# Schematic_proiect_v15.net
KiCad netlist of a schematic drawn in EAGLE
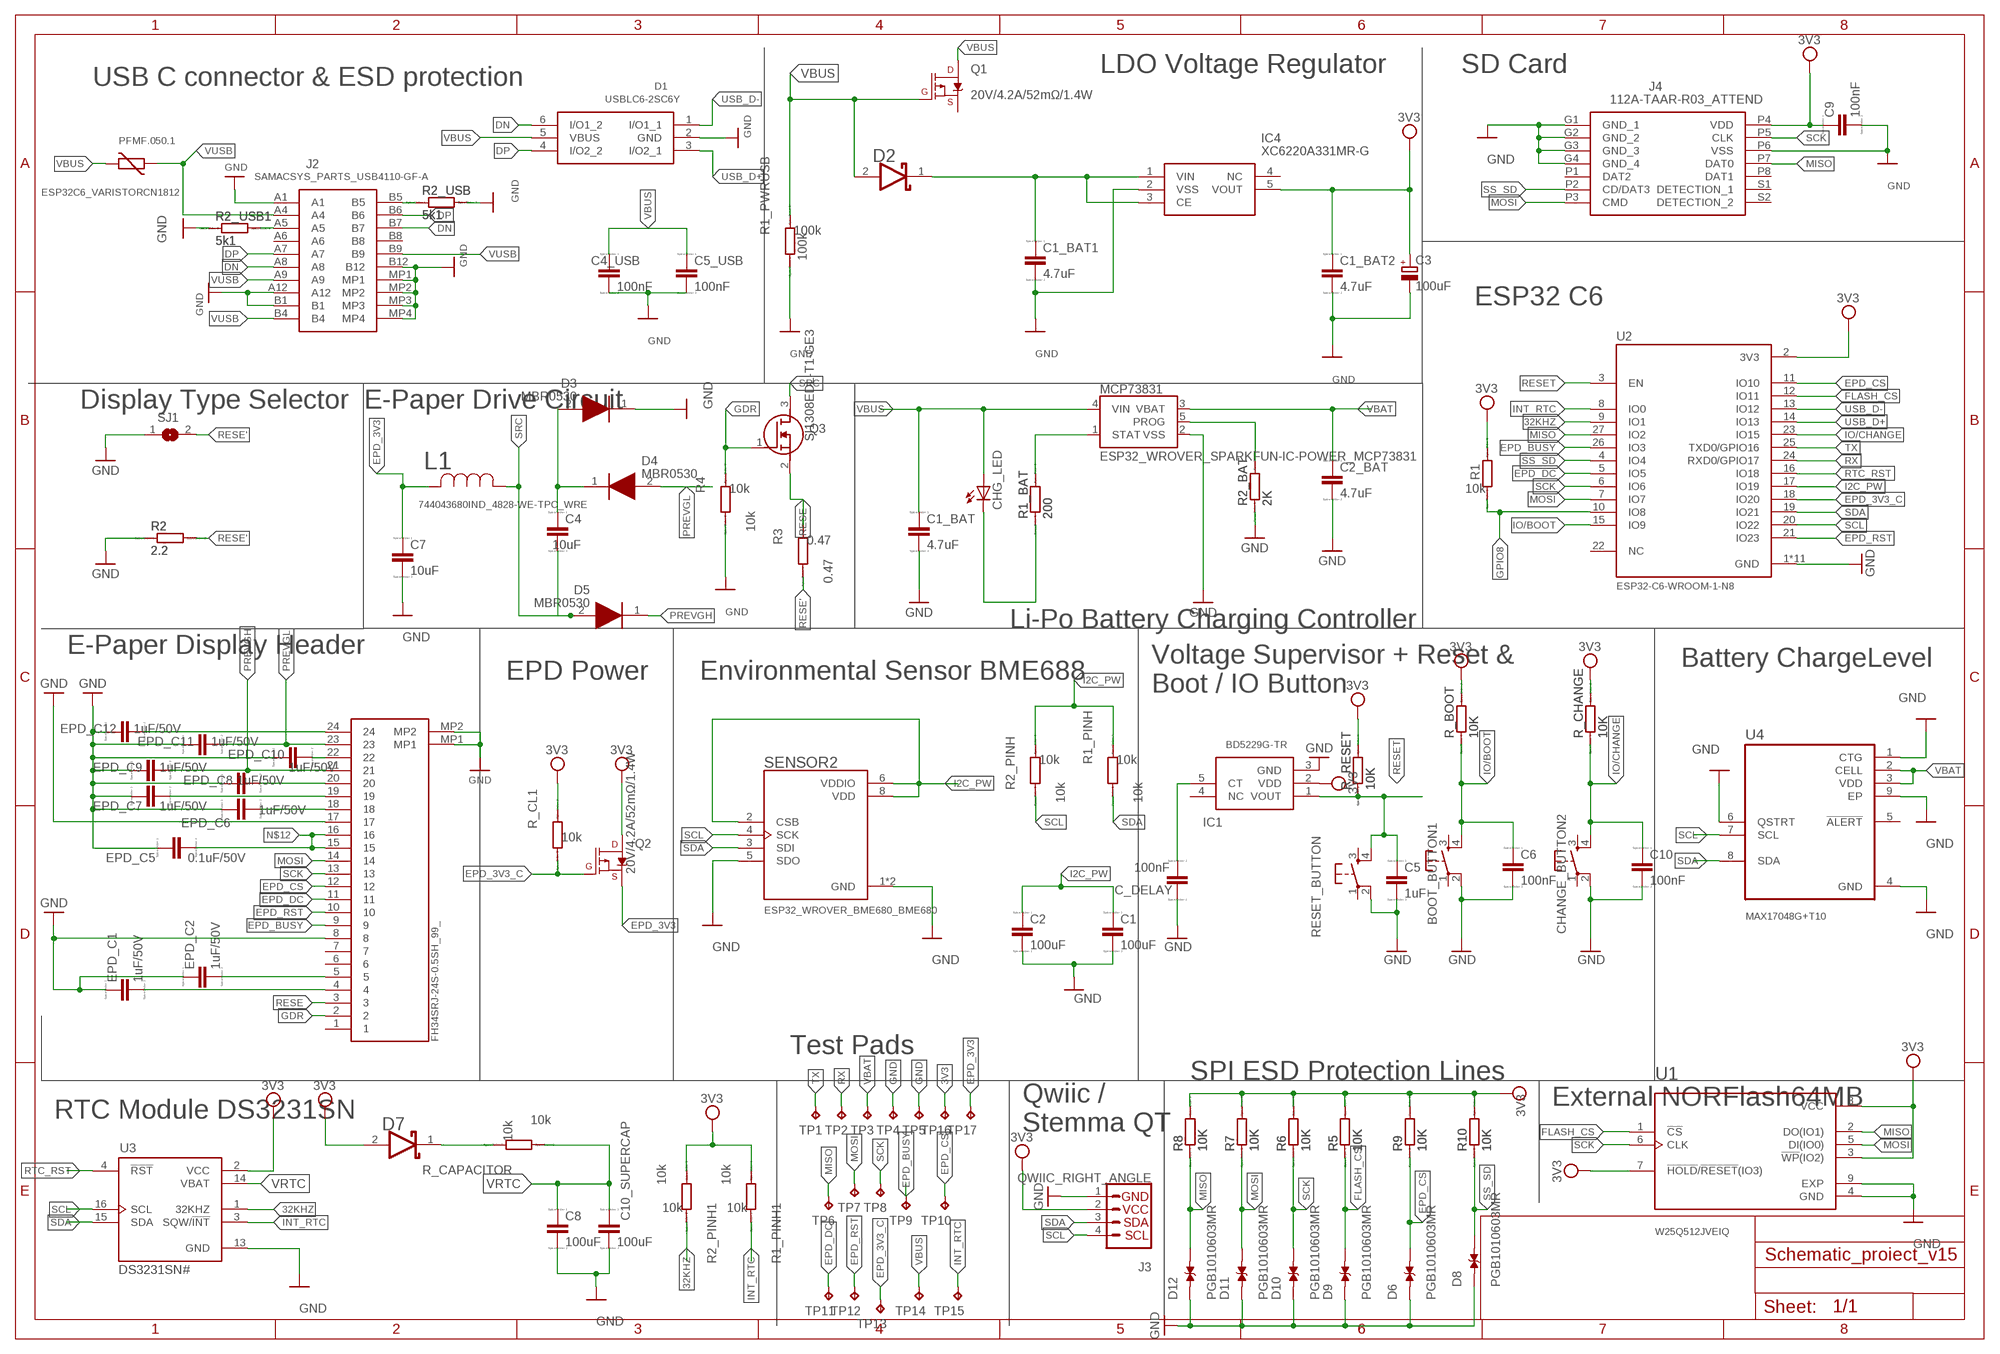
[diagram p0: schematic, sheet 1]

(export (version "E")
  (design (tool "Eeschema 10.0.6"))
  (components
    (comp (ref "BOOT_BUTTON1")
      (value "BUTTON_CUSYOMV1")
      (footprint "eagle-import:MYBUTTON")
      (libsource (lib "eagle-import") (part "BUTTON_CUSYOMV1"))
    )
    (comp (ref "C1")
      (value "100uF")
      (footprint "eagle-import:EAGLE-LTSPICE_C0402")
      (libsource (lib "eagle-import") (part "DeskAssistant v19 v1_vf.nBZE1evWTd-OCEZQXOw4Cw_EAGLE-LTSPICE_CC0402"))
    )
    (comp (ref "C1_BAT")
      (value "4.7uF")
      (footprint "eagle-import:EAGLE-LTSPICE_C0402")
      (libsource (lib "eagle-import") (part "EAGLE-LTSPICE_CC0402"))
    )
    (comp (ref "C1_BAT1")
      (value "4.7uF")
      (footprint "eagle-import:EAGLE-LTSPICE_C0402")
      (libsource (lib "eagle-import") (part "DeskAssistant v19 v1_vf.nBZE1evWTd-OCEZQXOw4Cw_EAGLE-LTSPICE_CC0402"))
    )
    (comp (ref "C1_BAT2")
      (value "4.7uF")
      (footprint "eagle-import:EAGLE-LTSPICE_C0402")
      (libsource (lib "eagle-import") (part "DeskAssistant v19 v1_vf.nBZE1evWTd-OCEZQXOw4Cw_EAGLE-LTSPICE_CC0402"))
    )
    (comp (ref "C2")
      (value "100uF")
      (footprint "eagle-import:EAGLE-LTSPICE_C0402")
      (libsource (lib "eagle-import") (part "DeskAssistant v19 v1_vf.nBZE1evWTd-OCEZQXOw4Cw_EAGLE-LTSPICE_CC0402"))
    )
    (comp (ref "C2_BAT")
      (value "4.7uF")
      (footprint "eagle-import:EAGLE-LTSPICE_C0402")
      (libsource (lib "eagle-import") (part "EAGLE-LTSPICE_CC0402"))
    )
    (comp (ref "C3")
      (value "100uF")
      (footprint "eagle-import:RCL_CT3528")
      (libsource (lib "eagle-import") (part "RCL_CPOL-EUCT3528"))
    )
    (comp (ref "C4")
      (value "10uF")
      (footprint "eagle-import:EAGLE-LTSPICE_C0402")
      (libsource (lib "eagle-import") (part "DeskAssistant v19 v1_vf.nBZE1evWTd-OCEZQXOw4Cw_EAGLE-LTSPICE_CC0402"))
    )
    (comp (ref "C4_USB")
      (value "100nF")
      (footprint "eagle-import:EAGLE-LTSPICE_C0402")
      (libsource (lib "eagle-import") (part "DeskAssistant v19 v1_vf.nBZE1evWTd-OCEZQXOw4Cw_EAGLE-LTSPICE_CC0402"))
    )
    (comp (ref "C5")
      (value "1uF")
      (footprint "eagle-import:EAGLE-LTSPICE_C0402")
      (libsource (lib "eagle-import") (part "EAGLE-LTSPICE_CC0402"))
    )
    (comp (ref "C5_USB")
      (value "100nF")
      (footprint "eagle-import:EAGLE-LTSPICE_C0402")
      (libsource (lib "eagle-import") (part "DeskAssistant v19 v1_vf.nBZE1evWTd-OCEZQXOw4Cw_EAGLE-LTSPICE_CC0402"))
    )
    (comp (ref "C6")
      (value "100nF")
      (footprint "eagle-import:EAGLE-LTSPICE_C0402")
      (libsource (lib "eagle-import") (part "EAGLE-LTSPICE_CC0402"))
    )
    (comp (ref "C7")
      (value "10uF")
      (footprint "eagle-import:EAGLE-LTSPICE_C0402")
      (libsource (lib "eagle-import") (part "DeskAssistant v19 v1_vf.nBZE1evWTd-OCEZQXOw4Cw_EAGLE-LTSPICE_CC0402"))
    )
    (comp (ref "C8")
      (value "100uF")
      (footprint "eagle-import:EAGLE-LTSPICE_C0402")
      (libsource (lib "eagle-import") (part "DeskAssistant v19 v1_vf.nBZE1evWTd-OCEZQXOw4Cw_EAGLE-LTSPICE_CC0402"))
    )
    (comp (ref "C9")
      (value "100nF")
      (footprint "eagle-import:EAGLE-LTSPICE_C0402")
      (libsource (lib "eagle-import") (part "DeskAssistant v19 v1_vf.nBZE1evWTd-OCEZQXOw4Cw_EAGLE-LTSPICE_CC0402"))
    )
    (comp (ref "C10")
      (value "100nF")
      (footprint "eagle-import:EAGLE-LTSPICE_C0402")
      (libsource (lib "eagle-import") (part "EAGLE-LTSPICE_CC0402"))
    )
    (comp (ref "C10_SUPERCAP")
      (value "100uF")
      (footprint "eagle-import:EAGLE-LTSPICE_C0402")
      (libsource (lib "eagle-import") (part "DeskAssistant v19 v1_vf.nBZE1evWTd-OCEZQXOw4Cw_EAGLE-LTSPICE_CC0402"))
    )
    (comp (ref "CHANGE_BUTTON2")
      (value "BUTTON_CUSYOMV1")
      (footprint "eagle-import:MYBUTTON")
      (libsource (lib "eagle-import") (part "BUTTON_CUSYOMV1"))
    )
    (comp (ref "CHG_LED")
      (value "ADAFRUIT_LEDCHIP-LED0603")
      (footprint "eagle-import:ADAFRUIT_CHIP-LED0603")
      (libsource (lib "eagle-import") (part "ADAFRUIT_LEDCHIP-LED0603"))
    )
    (comp (ref "C_DELAY")
      (value "100nF")
      (footprint "eagle-import:EAGLE-LTSPICE_C0402")
      (libsource (lib "eagle-import") (part "EAGLE-LTSPICE_CC0402"))
    )
    (comp (ref "D1")
      (value "USBLC6-2SC6Y")
      (footprint "eagle-import:SOT95P280X145-6N")
      (fields (field (name "MF") "STMicroelectronics"))
      (libsource (lib "eagle-import") (part "USBLC6-2SC6Y"))
    )
    (comp (ref "D2")
      (value "ESP32_WROVER_AVX---SD0805S020S1R0_AVX_SD0805S020S1R0_0_0AVX_SD0805S020S1R0_0_0")
      (footprint "eagle-import:ESP32_WROVER_AVX---SD0805S020S1R0_AVX_SD0805S020S1R0_0")
      (fields
        (field (name "DIGIKEY_PART_NUMBER") "478-7800-1-ND")
        (field (name "MF") "AVX")
        (field (name "MOUSER_PART_NUMBER") "581-SD0805S020S1R0")
      )
      (libsource (lib "eagle-import") (part "ESP32_WROVER_AVX---SD0805S020S1R0_AVX_SD0805S020S1R0_0_0AVX_SD0805S020S1R0_0_0"))
    )
    (comp (ref "D3")
      (value "MBR0530")
      (footprint "eagle-import:SOD3716X135N")
      (fields (field (name "MF") "ON Semiconductor"))
      (libsource (lib "eagle-import") (part "MBR0530"))
    )
    (comp (ref "D4")
      (value "MBR0530")
      (footprint "eagle-import:SOD3716X135N")
      (fields (field (name "MF") "ON Semiconductor"))
      (libsource (lib "eagle-import") (part "MBR0530"))
    )
    (comp (ref "D5")
      (value "MBR0530")
      (footprint "eagle-import:SOD3716X135N")
      (fields (field (name "MF") "ON Semiconductor"))
      (libsource (lib "eagle-import") (part "MBR0530"))
    )
    (comp (ref "D6")
      (value "PGB1010603MR")
      (footprint "eagle-import:DIOC1608X36N")
      (fields (field (name "MF") "Littelfuse Inc."))
      (libsource (lib "eagle-import") (part "PGB1010603MR"))
    )
    (comp (ref "D7")
      (value "ESP32_WROVER_AVX---SD0805S020S1R0_AVX_SD0805S020S1R0_0_0AVX_SD0805S020S1R0_0_0")
      (footprint "eagle-import:ESP32_WROVER_AVX---SD0805S020S1R0_AVX_SD0805S020S1R0_0")
      (fields
        (field (name "DIGIKEY_PART_NUMBER") "478-7800-1-ND")
        (field (name "MF") "AVX")
        (field (name "MOUSER_PART_NUMBER") "581-SD0805S020S1R0")
      )
      (libsource (lib "eagle-import") (part "ESP32_WROVER_AVX---SD0805S020S1R0_AVX_SD0805S020S1R0_0_0AVX_SD0805S020S1R0_0_0"))
    )
    (comp (ref "D8")
      (value "PGB1010603MR")
      (footprint "eagle-import:DIOC1608X36N")
      (fields (field (name "MF") "Littelfuse Inc."))
      (libsource (lib "eagle-import") (part "PGB1010603MR"))
    )
    (comp (ref "D9")
      (value "PGB1010603MR")
      (footprint "eagle-import:DIOC1608X36N")
      (fields (field (name "MF") "Littelfuse Inc."))
      (libsource (lib "eagle-import") (part "PGB1010603MR"))
    )
    (comp (ref "D10")
      (value "PGB1010603MR")
      (footprint "eagle-import:DIOC1608X36N")
      (fields (field (name "MF") "Littelfuse Inc."))
      (libsource (lib "eagle-import") (part "PGB1010603MR"))
    )
    (comp (ref "D11")
      (value "PGB1010603MR")
      (footprint "eagle-import:DIOC1608X36N")
      (fields (field (name "MF") "Littelfuse Inc."))
      (libsource (lib "eagle-import") (part "PGB1010603MR"))
    )
    (comp (ref "D12")
      (value "PGB1010603MR")
      (footprint "eagle-import:DIOC1608X36N")
      (fields (field (name "MF") "Littelfuse Inc."))
      (libsource (lib "eagle-import") (part "PGB1010603MR"))
    )
    (comp (ref "EPD_C1")
      (value "1uF/50V")
      (footprint "eagle-import:EAGLE-LTSPICE_C0402")
      (libsource (lib "eagle-import") (part "EAGLE-LTSPICE_CC0402"))
    )
    (comp (ref "EPD_C2")
      (value "1uF/50V")
      (footprint "eagle-import:EAGLE-LTSPICE_C0402")
      (libsource (lib "eagle-import") (part "EAGLE-LTSPICE_CC0402"))
    )
    (comp (ref "EPD_C5")
      (value "0.1uF/50V")
      (footprint "eagle-import:EAGLE-LTSPICE_C0402")
      (libsource (lib "eagle-import") (part "EAGLE-LTSPICE_CC0402"))
    )
    (comp (ref "EPD_C6")
      (value "1uF/50V")
      (footprint "eagle-import:EAGLE-LTSPICE_C0402")
      (libsource (lib "eagle-import") (part "EAGLE-LTSPICE_CC0402"))
    )
    (comp (ref "EPD_C7")
      (value "1uF/50V")
      (footprint "eagle-import:EAGLE-LTSPICE_C0402")
      (libsource (lib "eagle-import") (part "EAGLE-LTSPICE_CC0402"))
    )
    (comp (ref "EPD_C8")
      (value "1uF/50V")
      (footprint "eagle-import:EAGLE-LTSPICE_C0402")
      (libsource (lib "eagle-import") (part "EAGLE-LTSPICE_CC0402"))
    )
    (comp (ref "EPD_C9")
      (value "1uF/50V")
      (footprint "eagle-import:EAGLE-LTSPICE_C0402")
      (libsource (lib "eagle-import") (part "EAGLE-LTSPICE_CC0402"))
    )
    (comp (ref "EPD_C10")
      (value "1uF/50V")
      (footprint "eagle-import:EAGLE-LTSPICE_C0402")
      (libsource (lib "eagle-import") (part "EAGLE-LTSPICE_CC0402"))
    )
    (comp (ref "EPD_C11")
      (value "1uF/50V")
      (footprint "eagle-import:EAGLE-LTSPICE_C0402")
      (libsource (lib "eagle-import") (part "EAGLE-LTSPICE_CC0402"))
    )
    (comp (ref "EPD_C12")
      (value "1uF/50V")
      (footprint "eagle-import:EAGLE-LTSPICE_C0402")
      (libsource (lib "eagle-import") (part "EAGLE-LTSPICE_CC0402"))
    )
    (comp (ref "FH34SRJ-24S-0.5SH_99_")
      (value "FH34SRJ-24S-0.5SH_99_")
      (footprint "eagle-import:FH34SRJ24S05SH99")
      (fields
        (field (name "MANUFACTURER_PART_NUMBER") "FH34SRJ-24S-0.5SH(99)")
        (field (name "MOUSER_PART_NUMBER") "798-FH34SRJ24S05SH99")
      )
      (libsource (lib "eagle-import") (part "FH34SRJ-24S-0.5SH_99_"))
    )
    (comp (ref "IC1")
      (value "BD5229G-TR")
      (footprint "eagle-import:SOT95P280X125-5N")
      (fields (field (name "MOUSER_PART_NUMBER") "755-BD5229G-TR"))
      (libsource (lib "eagle-import") (part "BD5229G-TR"))
    )
    (comp (ref "IC4")
      (value "XC6220A331MR-G")
      (footprint "eagle-import:SOT95P280X120-5N")
      (fields (field (name "MOUSER_PART_NUMBER") "865-XC6220A331MR-G"))
      (libsource (lib "eagle-import") (part "XC6220A331MR-G"))
    )
    (comp (ref "J2")
      (value "SAMACSYS_PARTS_USB4110-GF-A")
      (footprint "eagle-import:SAMACSYS_PARTS_USB4110GFA")
      (fields
        (field (name "MANUFACTURER_PART_NUMBER") "USB4110-GF-A")
        (field (name "MOUSER_PART_NUMBER") "640-USB4110-GF-A")
      )
      (libsource (lib "eagle-import") (part "SAMACSYS_PARTS_USB4110-GF-A"))
    )
    (comp (ref "J3")
      (value "QWIIC_RIGHT_ANGLE")
      (footprint "eagle-import:JST04_1MM_RA")
      (libsource (lib "eagle-import") (part "QWIIC_CONNECTORJS-1MM"))
    )
    (comp (ref "J4")
      (value "112A-TAAR-R03_ATTEND")
      (footprint "eagle-import:112ATAARR03ATTEND")
      (fields (field (name "MANUFACTURER_PART_NUMBER") "112A-TAAR-R03 ATTEND"))
      (libsource (lib "eagle-import") (part "112A-TAAR-R03_ATTEND"))
    )
    (comp (ref "L1")
      (value "744043680IND_4828-WE-TPC_WRE")
      (footprint "eagle-import:IND_4828-WE-TPC_WRE")
      (fields
        (field (name "MANUFACTURER_PART_NUMBER") "744043680")
        (field (name "COPYRIGHT") "Copyright (C) 2024 Ultra Librarian. All rights reserved.")
      )
      (libsource (lib "eagle-import") (part "744043680IND_4828-WE-TPC_WRE"))
    )
    (comp (ref "MCP73831")
      (value "ESP32_WROVER_SPARKFUN-IC-POWER_MCP73831")
      (footprint "eagle-import:ESP32_WROVER_SPARKFUN-IC-POWER_SOT23-5")
      (libsource (lib "eagle-import") (part "ESP32_WROVER_SPARKFUN-IC-POWER_MCP73831"))
    )
    (comp (ref "PFMF.050.1")
      (value "ESP32C6_VARISTORCN1812")
      (footprint "eagle-import:ESP32C6_VARISTOR_CT_CN1812")
      (libsource (lib "eagle-import") (part "ESP32C6_VARISTORCN1812"))
    )
    (comp (ref "Q1")
      (value "20V/4.2A/52mΩ/1.4W")
      (footprint "eagle-import:ESP32_WROVER_SPARKFUN-DISCRETESEMI_SOT23-3")
      (libsource (lib "eagle-import") (part "ESP32_WROVER_SPARKFUN-DISCRETESEMI_MOSFET_PCH-DMG2305UX-7"))
    )
    (comp (ref "Q2")
      (value "20V/4.2A/52mΩ/1.4W")
      (footprint "eagle-import:ESP32_WROVER_SPARKFUN-DISCRETESEMI_SOT23-3")
      (libsource (lib "eagle-import") (part "ESP32_WROVER_SPARKFUN-DISCRETESEMI_MOSFET_PCH-DMG2305UX-7"))
    )
    (comp (ref "Q3")
      (value "SI1308EDL-T1-GE3")
      (footprint "eagle-import:SOT65P210X110-3N")
      (fields (field (name "MF") "Vishay Siliconix"))
      (libsource (lib "eagle-import") (part "SI1308EDL-T1-GE3"))
    )
    (comp (ref "R1")
      (value "10k")
      (footprint "eagle-import:ESP32_WROVER_EAGLE-LTSPICE_R0402")
      (libsource (lib "eagle-import") (part "DeskAssistant v19 v1_vf.nBZE1evWTd-OCEZQXOw4Cw_ESP32_WROVER_EAGLE-LTSPICE_RR0402"))
    )
    (comp (ref "R1_BAT")
      (value "200")
      (footprint "eagle-import:ESP32_WROVER_EAGLE-LTSPICE_R0402")
      (libsource (lib "eagle-import") (part "ESP32_WROVER_EAGLE-LTSPICE_RR0402"))
    )
    (comp (ref "R1_PINH")
      (value "10k")
      (footprint "eagle-import:ESP32_WROVER_EAGLE-LTSPICE_R0402")
      (libsource (lib "eagle-import") (part "DeskAssistant v19 v1_vf.nBZE1evWTd-OCEZQXOw4Cw_ESP32_WROVER_EAGLE-LTSPICE_RR0402"))
    )
    (comp (ref "R1_PINH1")
      (value "10k")
      (footprint "eagle-import:ESP32_WROVER_EAGLE-LTSPICE_R0402")
      (libsource (lib "eagle-import") (part "DeskAssistant v19 v1_vf.nBZE1evWTd-OCEZQXOw4Cw_ESP32_WROVER_EAGLE-LTSPICE_RR0402"))
    )
    (comp (ref "R1_PWRUSB")
      (value "100k")
      (footprint "eagle-import:ESP32_WROVER_EAGLE-LTSPICE_R0402")
      (libsource (lib "eagle-import") (part "DeskAssistant v19 v1_vf.nBZE1evWTd-OCEZQXOw4Cw_ESP32_WROVER_EAGLE-LTSPICE_RR0402"))
    )
    (comp (ref "R2")
      (value "2.2")
      (footprint "eagle-import:ESP32_WROVER_EAGLE-LTSPICE_R0402")
      (libsource (lib "eagle-import") (part "ESP32_WROVER_EAGLE-LTSPICE_RR0402"))
    )
    (comp (ref "R2_BAT")
      (value "2K")
      (footprint "eagle-import:ESP32_WROVER_EAGLE-LTSPICE_R0402")
      (libsource (lib "eagle-import") (part "ESP32_WROVER_EAGLE-LTSPICE_RR0402"))
    )
    (comp (ref "R2_PINH")
      (value "10k")
      (footprint "eagle-import:ESP32_WROVER_EAGLE-LTSPICE_R0402")
      (libsource (lib "eagle-import") (part "DeskAssistant v19 v1_vf.nBZE1evWTd-OCEZQXOw4Cw_ESP32_WROVER_EAGLE-LTSPICE_RR0402"))
    )
    (comp (ref "R2_PINH1")
      (value "10k")
      (footprint "eagle-import:ESP32_WROVER_EAGLE-LTSPICE_R0402")
      (libsource (lib "eagle-import") (part "DeskAssistant v19 v1_vf.nBZE1evWTd-OCEZQXOw4Cw_ESP32_WROVER_EAGLE-LTSPICE_RR0402"))
    )
    (comp (ref "R2_USB")
      (value "5k1")
      (footprint "eagle-import:ESP32_WROVER_EAGLE-LTSPICE_R0402")
      (libsource (lib "eagle-import") (part "DeskAssistant v19 v1_vf.nBZE1evWTd-OCEZQXOw4Cw_ESP32_WROVER_EAGLE-LTSPICE_RR0402"))
    )
    (comp (ref "R2_USB1")
      (value "5k1")
      (footprint "eagle-import:ESP32_WROVER_EAGLE-LTSPICE_R0402")
      (libsource (lib "eagle-import") (part "DeskAssistant v19 v1_vf.nBZE1evWTd-OCEZQXOw4Cw_ESP32_WROVER_EAGLE-LTSPICE_RR0402"))
    )
    (comp (ref "R3")
      (value "0.47")
      (footprint "eagle-import:ESP32_WROVER_EAGLE-LTSPICE_R0402")
      (libsource (lib "eagle-import") (part "DeskAssistant v19 v1_vf.nBZE1evWTd-OCEZQXOw4Cw_ESP32_WROVER_EAGLE-LTSPICE_RR0402"))
    )
    (comp (ref "R4")
      (value "10k")
      (footprint "eagle-import:ESP32_WROVER_EAGLE-LTSPICE_R0402")
      (libsource (lib "eagle-import") (part "DeskAssistant v19 v1_vf.nBZE1evWTd-OCEZQXOw4Cw_ESP32_WROVER_EAGLE-LTSPICE_RR0402"))
    )
    (comp (ref "R5")
      (value "10K")
      (footprint "eagle-import:ESP32_WROVER_EAGLE-LTSPICE_R0402")
      (libsource (lib "eagle-import") (part "ESP32_WROVER_EAGLE-LTSPICE_RR0402"))
    )
    (comp (ref "R6")
      (value "10K")
      (footprint "eagle-import:ESP32_WROVER_EAGLE-LTSPICE_R0402")
      (libsource (lib "eagle-import") (part "ESP32_WROVER_EAGLE-LTSPICE_RR0402"))
    )
    (comp (ref "R7")
      (value "10K")
      (footprint "eagle-import:ESP32_WROVER_EAGLE-LTSPICE_R0402")
      (libsource (lib "eagle-import") (part "ESP32_WROVER_EAGLE-LTSPICE_RR0402"))
    )
    (comp (ref "R8")
      (value "10K")
      (footprint "eagle-import:ESP32_WROVER_EAGLE-LTSPICE_R0402")
      (libsource (lib "eagle-import") (part "ESP32_WROVER_EAGLE-LTSPICE_RR0402"))
    )
    (comp (ref "R9")
      (value "10K")
      (footprint "eagle-import:ESP32_WROVER_EAGLE-LTSPICE_R0402")
      (libsource (lib "eagle-import") (part "ESP32_WROVER_EAGLE-LTSPICE_RR0402"))
    )
    (comp (ref "R10")
      (value "10K")
      (footprint "eagle-import:ESP32_WROVER_EAGLE-LTSPICE_R0402")
      (libsource (lib "eagle-import") (part "ESP32_WROVER_EAGLE-LTSPICE_RR0402"))
    )
    (comp (ref "RESET_BUTTON")
      (value "BUTTON_CUSYOMV1")
      (footprint "eagle-import:MYBUTTON")
      (libsource (lib "eagle-import") (part "BUTTON_CUSYOMV1"))
    )
    (comp (ref "R_BOOT")
      (value "10K")
      (footprint "eagle-import:ESP32_WROVER_EAGLE-LTSPICE_R0402")
      (libsource (lib "eagle-import") (part "ESP32_WROVER_EAGLE-LTSPICE_RR0402"))
    )
    (comp (ref "R_CAPACITOR")
      (value "10k")
      (footprint "eagle-import:ESP32_WROVER_EAGLE-LTSPICE_R0402")
      (libsource (lib "eagle-import") (part "DeskAssistant v19 v1_vf.nBZE1evWTd-OCEZQXOw4Cw_ESP32_WROVER_EAGLE-LTSPICE_RR0402"))
    )
    (comp (ref "R_CHANGE")
      (value "10K")
      (footprint "eagle-import:ESP32_WROVER_EAGLE-LTSPICE_R0402")
      (libsource (lib "eagle-import") (part "ESP32_WROVER_EAGLE-LTSPICE_RR0402"))
    )
    (comp (ref "R_CL1")
      (value "10k")
      (footprint "eagle-import:ESP32_WROVER_EAGLE-LTSPICE_R0402")
      (libsource (lib "eagle-import") (part "DeskAssistant v19 v1_vf.nBZE1evWTd-OCEZQXOw4Cw_ESP32_WROVER_EAGLE-LTSPICE_RR0402"))
    )
    (comp (ref "R_RESET")
      (value "10K")
      (footprint "eagle-import:ESP32_WROVER_EAGLE-LTSPICE_R0402")
      (libsource (lib "eagle-import") (part "ESP32_WROVER_EAGLE-LTSPICE_RR0402"))
    )
    (comp (ref "SENSOR2")
      (value "ESP32_WROVER_BME680_BME680")
      (footprint "eagle-import:ESP32_WROVER_BME680_PSON80P300X300X100-8N")
      (fields (field (name "MF") "Bosch Sensortec") (field (name "MP") "BME680"))
      (libsource (lib "eagle-import") (part "ESP32_WROVER_BME680_BME680"))
    )
    (comp (ref "SJ1") (value "SJ") (footprint "eagle-import:SJ") (libsource (lib "eagle-import") (part "SJ")))
    (comp (ref "TP1")
      (value "TPTP20R")
      (footprint "eagle-import:TP20R")
      (libsource (lib "eagle-import") (part "TPTP20R"))
    )
    (comp (ref "TP2")
      (value "TPTP20R")
      (footprint "eagle-import:TP20R")
      (libsource (lib "eagle-import") (part "TPTP20R"))
    )
    (comp (ref "TP3")
      (value "TPTP20R")
      (footprint "eagle-import:TP20R")
      (libsource (lib "eagle-import") (part "TPTP20R"))
    )
    (comp (ref "TP4")
      (value "TPTP20R")
      (footprint "eagle-import:TP20R")
      (libsource (lib "eagle-import") (part "TPTP20R"))
    )
    (comp (ref "TP5")
      (value "TPTP20R")
      (footprint "eagle-import:TP20R")
      (libsource (lib "eagle-import") (part "TPTP20R"))
    )
    (comp (ref "TP6")
      (value "TPTP20R")
      (footprint "eagle-import:TP20R")
      (libsource (lib "eagle-import") (part "TPTP20R"))
    )
    (comp (ref "TP7")
      (value "TPTP20R")
      (footprint "eagle-import:TP20R")
      (libsource (lib "eagle-import") (part "TPTP20R"))
    )
    (comp (ref "TP8")
      (value "TPTP20R")
      (footprint "eagle-import:TP20R")
      (libsource (lib "eagle-import") (part "TPTP20R"))
    )
    (comp (ref "TP9")
      (value "TPTP20R")
      (footprint "eagle-import:TP20R")
      (libsource (lib "eagle-import") (part "TPTP20R"))
    )
    (comp (ref "TP10")
      (value "TPTP20R")
      (footprint "eagle-import:TP20R")
      (libsource (lib "eagle-import") (part "TPTP20R"))
    )
    (comp (ref "TP11")
      (value "TPTP20R")
      (footprint "eagle-import:TP20R")
      (libsource (lib "eagle-import") (part "TPTP20R"))
    )
    (comp (ref "TP12")
      (value "TPTP20R")
      (footprint "eagle-import:TP20R")
      (libsource (lib "eagle-import") (part "TPTP20R"))
    )
    (comp (ref "TP13")
      (value "TPTP20R")
      (footprint "eagle-import:TP20R")
      (libsource (lib "eagle-import") (part "TPTP20R"))
    )
    (comp (ref "TP14")
      (value "TPTP20R")
      (footprint "eagle-import:TP20R")
      (libsource (lib "eagle-import") (part "TPTP20R"))
    )
    (comp (ref "TP15")
      (value "TPTP20R")
      (footprint "eagle-import:TP20R")
      (libsource (lib "eagle-import") (part "TPTP20R"))
    )
    (comp (ref "TP16")
      (value "TPTP20R")
      (footprint "eagle-import:TP20R")
      (libsource (lib "eagle-import") (part "TPTP20R"))
    )
    (comp (ref "TP17")
      (value "TPTP20R")
      (footprint "eagle-import:TP20R")
      (libsource (lib "eagle-import") (part "TPTP20R"))
    )
    (comp (ref "U1")
      (value "W25Q512JVEIQ")
      (footprint "eagle-import:SON127P600X800X80-9N")
      (fields (field (name "MF") "Winbond Electronics"))
      (libsource (lib "eagle-import") (part "W25Q512JVEIQ"))
    )
    (comp (ref "U2")
      (value "ESP32-C6-WROOM-1-N8")
      (footprint "eagle-import:XCVR_ESP32-C6-WROOM-1-N8")
      (fields (field (name "MF") "Espressif Systems"))
      (libsource (lib "eagle-import") (part "ESP32-C6-WROOM-1-N8"))
    )
    (comp (ref "U3")
      (value "DS3231SN#")
      (footprint "eagle-import:SOIC127P1032X265-16N")
      (fields (field (name "MF") "Analog Devices"))
      (libsource (lib "eagle-import") (part "DS3231SN#"))
    )
    (comp (ref "U4")
      (value "MAX17048G+T10")
      (footprint "eagle-import:SON50P200X200X80-9N")
      (fields (field (name "MF") "Analog Devices"))
      (libsource (lib "eagle-import") (part "MAX17048G+T10"))
    )
  )
  (nets
    (net (code "1") (name "3V3") (class "Default")
      (node (ref "C1_BAT2") (pin "1") (pinfunction "1_1") (pintype "passive"))
      (node (ref "C3") (pin "+") (pinfunction "+_+") (pintype "passive"))
      (node (ref "C9") (pin "1") (pinfunction "1_1") (pintype "passive"))
      (node (ref "D7") (pin "2") (pinfunction "ANODE_2") (pintype "bidirectional"))
      (node (ref "IC1") (pin "2") (pinfunction "VDD_2") (pintype "bidirectional"))
      (node (ref "IC4") (pin "5") (pinfunction "VOUT_5") (pintype "bidirectional"))
      (node (ref "J3") (pin "2") (pinfunction "2_2") (pintype "power_in"))
      (node (ref "J4") (pin "P4") (pinfunction "VDD_P4") (pintype "bidirectional"))
      (node (ref "Q2") (pin "3") (pinfunction "D_3") (pintype "bidirectional"))
      (node (ref "R1") (pin "2") (pinfunction "2_2") (pintype "passive"))
      (node (ref "R10") (pin "2") (pinfunction "2_2") (pintype "passive"))
      (node (ref "R1_PINH1") (pin "1") (pinfunction "1_1") (pintype "passive"))
      (node (ref "R2_PINH1") (pin "1") (pinfunction "1_1") (pintype "passive"))
      (node (ref "R5") (pin "2") (pinfunction "2_2") (pintype "passive"))
      (node (ref "R6") (pin "2") (pinfunction "2_2") (pintype "passive"))
      (node (ref "R7") (pin "2") (pinfunction "2_2") (pintype "passive"))
      (node (ref "R8") (pin "2") (pinfunction "2_2") (pintype "passive"))
      (node (ref "R9") (pin "2") (pinfunction "2_2") (pintype "passive"))
      (node (ref "R_BOOT") (pin "2") (pinfunction "2_2") (pintype "passive"))
      (node (ref "R_CHANGE") (pin "2") (pinfunction "2_2") (pintype "passive"))
      (node (ref "R_CL1") (pin "2") (pinfunction "2_2") (pintype "passive"))
      (node (ref "R_RESET") (pin "2") (pinfunction "2_2") (pintype "passive"))
      (node (ref "TP16") (pin "TP") (pinfunction "TP_TP") (pintype "input"))
      (node (ref "U1") (pin "3") (pinfunction "~{WP}(IO2)_3") (pintype "bidirectional"))
      (node (ref "U1") (pin "7") (pinfunction "~{HOLD}/~{RESET}(IO3)_7") (pintype "bidirectional"))
      (node (ref "U1") (pin "8") (pinfunction "VCC_8") (pintype "power_in"))
      (node (ref "U2") (pin "2") (pinfunction "3V3_2") (pintype "power_in"))
      (node (ref "U3") (pin "2") (pinfunction "VCC_2") (pintype "power_in"))
    )
    (net (code "2") (name "32KHZ") (class "Default")
      (node (ref "R2_PINH1") (pin "2") (pinfunction "2_2") (pintype "passive"))
      (node (ref "U2") (pin "9") (pinfunction "IO1_9") (pintype "bidirectional"))
      (node (ref "U3") (pin "1") (pinfunction "32KHZ_1") (pintype "output"))
    )
    (net (code "3") (name "DN") (class "Default")
      (node (ref "D1") (pin "6") (pinfunction "I/O1_2_6") (pintype "bidirectional"))
      (node (ref "J2") (pin "A8") (pinfunction "A8_A8") (pintype "bidirectional"))
      (node (ref "J2") (pin "B7") (pinfunction "B7_B7") (pintype "bidirectional"))
    )
    (net (code "4") (name "DP") (class "Default")
      (node (ref "D1") (pin "4") (pinfunction "I/O2_2_4") (pintype "bidirectional"))
      (node (ref "J2") (pin "A7") (pinfunction "A7_A7") (pintype "bidirectional"))
      (node (ref "J2") (pin "B6") (pinfunction "B6_B6") (pintype "bidirectional"))
    )
    (net (code "5") (name "EPD_3V3") (class "Default")
      (node (ref "C7") (pin "1") (pinfunction "1_1") (pintype "passive"))
      (node (ref "L1") (pin "2") (pinfunction "2_2") (pintype "passive"))
      (node (ref "Q2") (pin "2") (pinfunction "S_2") (pintype "bidirectional"))
      (node (ref "TP17") (pin "TP") (pinfunction "TP_TP") (pintype "input"))
    )
    (net (code "6") (name "EPD_3V3_C") (class "Default")
      (node (ref "Q2") (pin "1") (pinfunction "G_1") (pintype "bidirectional"))
      (node (ref "R_CL1") (pin "1") (pinfunction "1_1") (pintype "passive"))
      (node (ref "TP13") (pin "TP") (pinfunction "TP_TP") (pintype "input"))
      (node (ref "U2") (pin "18") (pinfunction "IO20_18") (pintype "bidirectional"))
    )
    (net (code "7") (name "EPD_BUSY") (class "Default")
      (node (ref "FH34SRJ-24S-0.5SH_99_") (pin "9") (pinfunction "9_9") (pintype "bidirectional"))
      (node (ref "TP9") (pin "TP") (pinfunction "TP_TP") (pintype "input"))
      (node (ref "U2") (pin "26") (pinfunction "IO3_26") (pintype "bidirectional"))
    )
    (net (code "8") (name "EPD_CS") (class "Default")
      (node (ref "D6") (pin "2") (pinfunction "2_2") (pintype "passive"))
      (node (ref "FH34SRJ-24S-0.5SH_99_") (pin "12") (pinfunction "12_12") (pintype "bidirectional"))
      (node (ref "R9") (pin "1") (pinfunction "1_1") (pintype "passive"))
      (node (ref "TP10") (pin "TP") (pinfunction "TP_TP") (pintype "input"))
      (node (ref "U2") (pin "11") (pinfunction "IO10_11") (pintype "bidirectional"))
    )
    (net (code "9") (name "EPD_DC") (class "Default")
      (node (ref "FH34SRJ-24S-0.5SH_99_") (pin "11") (pinfunction "11_11") (pintype "bidirectional"))
      (node (ref "TP11") (pin "TP") (pinfunction "TP_TP") (pintype "input"))
      (node (ref "U2") (pin "5") (pinfunction "IO5_5") (pintype "bidirectional"))
    )
    (net (code "10") (name "EPD_RST") (class "Default")
      (node (ref "FH34SRJ-24S-0.5SH_99_") (pin "10") (pinfunction "10_10") (pintype "bidirectional"))
      (node (ref "TP12") (pin "TP") (pinfunction "TP_TP") (pintype "input"))
      (node (ref "U2") (pin "21") (pinfunction "IO23_21") (pintype "bidirectional"))
    )
    (net (code "11") (name "FLASH_CS") (class "Default")
      (node (ref "D9") (pin "2") (pinfunction "2_2") (pintype "passive"))
      (node (ref "R5") (pin "1") (pinfunction "1_1") (pintype "passive"))
      (node (ref "U1") (pin "1") (pinfunction "~{CS}_1") (pintype "input"))
      (node (ref "U2") (pin "12") (pinfunction "IO11_12") (pintype "bidirectional"))
    )
    (net (code "12") (name "GDR") (class "Default")
      (node (ref "FH34SRJ-24S-0.5SH_99_") (pin "2") (pinfunction "2_2") (pintype "bidirectional"))
      (node (ref "Q3") (pin "1") (pinfunction "G_1") (pintype "bidirectional"))
      (node (ref "R4") (pin "2") (pinfunction "2_2") (pintype "passive"))
    )
    (net (code "13") (name "GND") (class "Default")
      (node (ref "BOOT_BUTTON1") (pin "2") (pinfunction "2_2") (pintype "passive"))
      (node (ref "C1") (pin "2") (pinfunction "2_2") (pintype "passive"))
      (node (ref "C10") (pin "2") (pinfunction "2_2") (pintype "passive"))
      (node (ref "C10_SUPERCAP") (pin "2") (pinfunction "2_2") (pintype "passive"))
      (node (ref "C1_BAT") (pin "2") (pinfunction "2_2") (pintype "passive"))
      (node (ref "C1_BAT1") (pin "2") (pinfunction "2_2") (pintype "passive"))
      (node (ref "C1_BAT2") (pin "2") (pinfunction "2_2") (pintype "passive"))
      (node (ref "C2") (pin "2") (pinfunction "2_2") (pintype "passive"))
      (node (ref "C2_BAT") (pin "2") (pinfunction "2_2") (pintype "passive"))
      (node (ref "C3") (pin "-") (pinfunction "-_-") (pintype "passive"))
      (node (ref "C4_USB") (pin "2") (pinfunction "2_2") (pintype "passive"))
      (node (ref "C5") (pin "2") (pinfunction "2_2") (pintype "passive"))
      (node (ref "C5_USB") (pin "2") (pinfunction "2_2") (pintype "passive"))
      (node (ref "C6") (pin "2") (pinfunction "2_2") (pintype "passive"))
      (node (ref "C7") (pin "2") (pinfunction "2_2") (pintype "passive"))
      (node (ref "C8") (pin "2") (pinfunction "2_2") (pintype "passive"))
      (node (ref "C9") (pin "2") (pinfunction "2_2") (pintype "passive"))
      (node (ref "CHANGE_BUTTON2") (pin "2") (pinfunction "2_2") (pintype "passive"))
      (node (ref "C_DELAY") (pin "1") (pinfunction "1_1") (pintype "passive"))
      (node (ref "D1") (pin "2") (pinfunction "GND_2") (pintype "bidirectional"))
      (node (ref "D10") (pin "1") (pinfunction "1_1") (pintype "passive"))
      (node (ref "D11") (pin "1") (pinfunction "1_1") (pintype "passive"))
      (node (ref "D12") (pin "1") (pinfunction "1_1") (pintype "passive"))
      (node (ref "D3") (pin "1") (pinfunction "K_1") (pintype "bidirectional"))
      (node (ref "D6") (pin "1") (pinfunction "1_1") (pintype "passive"))
      (node (ref "D8") (pin "1") (pinfunction "1_1") (pintype "passive"))
      (node (ref "D9") (pin "1") (pinfunction "1_1") (pintype "passive"))
      (node (ref "EPD_C1") (pin "1") (pinfunction "1_1") (pintype "passive"))
      (node (ref "EPD_C10") (pin "1") (pinfunction "1_1") (pintype "passive"))
      (node (ref "EPD_C11") (pin "1") (pinfunction "1_1") (pintype "passive"))
      (node (ref "EPD_C12") (pin "1") (pinfunction "1_1") (pintype "passive"))
      (node (ref "EPD_C2") (pin "1") (pinfunction "1_1") (pintype "passive"))
      (node (ref "EPD_C5") (pin "1") (pinfunction "1_1") (pintype "passive"))
      (node (ref "EPD_C6") (pin "1") (pinfunction "1_1") (pintype "passive"))
      (node (ref "EPD_C7") (pin "1") (pinfunction "1_1") (pintype "passive"))
      (node (ref "EPD_C8") (pin "1") (pinfunction "1_1") (pintype "passive"))
      (node (ref "EPD_C9") (pin "1") (pinfunction "1_1") (pintype "passive"))
      (node (ref "FH34SRJ-24S-0.5SH_99_") (pin "17") (pinfunction "17_17") (pintype "bidirectional"))
      (node (ref "FH34SRJ-24S-0.5SH_99_") (pin "8") (pinfunction "8_8") (pintype "bidirectional"))
      (node (ref "FH34SRJ-24S-0.5SH_99_") (pin "MP1") (pinfunction "MP1_MP1") (pintype "bidirectional"))
      (node (ref "FH34SRJ-24S-0.5SH_99_") (pin "MP2") (pinfunction "MP2_MP2") (pintype "bidirectional"))
      (node (ref "IC1") (pin "3") (pinfunction "GND_3") (pintype "bidirectional"))
      (node (ref "IC4") (pin "2") (pinfunction "VSS_2") (pintype "bidirectional"))
      (node (ref "J2") (pin "A1") (pinfunction "A1_A1") (pintype "bidirectional"))
      (node (ref "J2") (pin "A12") (pinfunction "A12_A12") (pintype "bidirectional"))
      (node (ref "J2") (pin "B1") (pinfunction "B1_B1") (pintype "bidirectional"))
      (node (ref "J2") (pin "B12") (pinfunction "B12_B12") (pintype "bidirectional"))
      (node (ref "J2") (pin "MP1") (pinfunction "MP1_MP1") (pintype "bidirectional"))
      (node (ref "J2") (pin "MP2") (pinfunction "MP2_MP2") (pintype "bidirectional"))
      (node (ref "J2") (pin "MP3") (pinfunction "MP3_MP3") (pintype "bidirectional"))
      (node (ref "J2") (pin "MP4") (pinfunction "MP4_MP4") (pintype "bidirectional"))
      (node (ref "J3") (pin "1") (pinfunction "1_1") (pintype "power_in"))
      (node (ref "J4") (pin "G1") (pinfunction "GND_1_G1") (pintype "bidirectional"))
      (node (ref "J4") (pin "G2") (pinfunction "GND_2_G2") (pintype "bidirectional"))
      (node (ref "J4") (pin "G3") (pinfunction "GND_3_G3") (pintype "bidirectional"))
      (node (ref "J4") (pin "G4") (pinfunction "GND_4_G4") (pintype "bidirectional"))
      (node (ref "J4") (pin "P6") (pinfunction "VSS_P6") (pintype "bidirectional"))
      (node (ref "MCP73831") (pin "2") (pinfunction "VSS_2") (pintype "power_in"))
      (node (ref "R1_PWRUSB") (pin "1") (pinfunction "1_1") (pintype "passive"))
      (node (ref "R2") (pin "1") (pinfunction "1_1") (pintype "passive"))
      (node (ref "R2_BAT") (pin "1") (pinfunction "1_1") (pintype "passive"))
      (node (ref "R2_USB") (pin "2") (pinfunction "2_2") (pintype "passive"))
      (node (ref "R2_USB1") (pin "1") (pinfunction "1_1") (pintype "passive"))
      (node (ref "R4") (pin "1") (pinfunction "1_1") (pintype "passive"))
      (node (ref "RESET_BUTTON") (pin "2") (pinfunction "2_2") (pintype "passive"))
      (node (ref "SENSOR2") (pin "1") (pinfunction "GND_1") (pintype "power_in"))
      (node (ref "SENSOR2") (pin "5") (pinfunction "SDO_5") (pintype "bidirectional"))
      (node (ref "SENSOR2") (pin "7") (pinfunction "GND_7") (pintype "power_in"))
      (node (ref "SJ1") (pin "1") (pinfunction "1_1") (pintype "passive"))
      (node (ref "TP4") (pin "TP") (pinfunction "TP_TP") (pintype "input"))
      (node (ref "TP5") (pin "TP") (pinfunction "TP_TP") (pintype "input"))
      (node (ref "U1") (pin "4") (pinfunction "GND_4") (pintype "power_in"))
      (node (ref "U1") (pin "9") (pinfunction "EXP_9") (pintype "passive"))
      (node (ref "U2") (pin "1") (pinfunction "GND_1") (pintype "power_in"))
      (node (ref "U2") (pin "28") (pinfunction "GND_28") (pintype "power_in"))
      (node (ref "U2") (pin "29_1") (pinfunction "GND_29_1") (pintype "power_in"))
      (node (ref "U2") (pin "29_2") (pinfunction "GND_29_2") (pintype "power_in"))
      (node (ref "U2") (pin "29_3") (pinfunction "GND_29_3") (pintype "power_in"))
      (node (ref "U2") (pin "29_4") (pinfunction "GND_29_4") (pintype "power_in"))
      (node (ref "U2") (pin "29_5") (pinfunction "GND_29_5") (pintype "power_in"))
      (node (ref "U2") (pin "29_6") (pinfunction "GND_29_6") (pintype "power_in"))
      (node (ref "U2") (pin "29_7") (pinfunction "GND_29_7") (pintype "power_in"))
      (node (ref "U2") (pin "29_8") (pinfunction "GND_29_8") (pintype "power_in"))
      (node (ref "U2") (pin "29_9") (pinfunction "GND_29_9") (pintype "power_in"))
      (node (ref "U3") (pin "13") (pinfunction "GND_13") (pintype "power_in"))
      (node (ref "U4") (pin "1") (pinfunction "CTG_1") (pintype "power_in"))
      (node (ref "U4") (pin "4") (pinfunction "GND_4") (pintype "power_in"))
      (node (ref "U4") (pin "6") (pinfunction "QSTRT_6") (pintype "input"))
      (node (ref "U4") (pin "9") (pinfunction "EP_9") (pintype "power_in"))
    )
    (net (code "14") (name "GPIO8") (class "Default")
      (node (ref "R1") (pin "1") (pinfunction "1_1") (pintype "passive"))
      (node (ref "U2") (pin "10") (pinfunction "IO8_10") (pintype "bidirectional"))
    )
    (net (code "15") (name "I2C_PW") (class "Default")
      (node (ref "C1") (pin "1") (pinfunction "1_1") (pintype "passive"))
      (node (ref "C2") (pin "1") (pinfunction "1_1") (pintype "passive"))
      (node (ref "R1_PINH") (pin "2") (pinfunction "2_2") (pintype "passive"))
      (node (ref "R2_PINH") (pin "2") (pinfunction "2_2") (pintype "passive"))
      (node (ref "SENSOR2") (pin "2") (pinfunction "CSB_2") (pintype "input"))
      (node (ref "SENSOR2") (pin "6") (pinfunction "VDDIO_6") (pintype "power_in"))
      (node (ref "SENSOR2") (pin "8") (pinfunction "VDD_8") (pintype "power_in"))
      (node (ref "U2") (pin "17") (pinfunction "IO19_17") (pintype "bidirectional"))
    )
    (net (code "16") (name "INT_RTC") (class "Default")
      (node (ref "R1_PINH1") (pin "2") (pinfunction "2_2") (pintype "passive"))
      (node (ref "TP15") (pin "TP") (pinfunction "TP_TP") (pintype "input"))
      (node (ref "U2") (pin "8") (pinfunction "IO0_8") (pintype "bidirectional"))
      (node (ref "U3") (pin "3") (pinfunction "SQW/~{INT}_3") (pintype "output"))
    )
    (net (code "17") (name "IO{slash}BOOT") (class "Default")
      (node (ref "BOOT_BUTTON1") (pin "4") (pinfunction "4_4") (pintype "passive"))
      (node (ref "C6") (pin "1") (pinfunction "1_1") (pintype "passive"))
      (node (ref "R_BOOT") (pin "1") (pinfunction "1_1") (pintype "passive"))
      (node (ref "U2") (pin "15") (pinfunction "IO9_15") (pintype "bidirectional"))
    )
    (net (code "18") (name "IO{slash}CHANGE") (class "Default")
      (node (ref "C10") (pin "1") (pinfunction "1_1") (pintype "passive"))
      (node (ref "CHANGE_BUTTON2") (pin "4") (pinfunction "4_4") (pintype "passive"))
      (node (ref "R_CHANGE") (pin "1") (pinfunction "1_1") (pintype "passive"))
      (node (ref "U2") (pin "23") (pinfunction "IO15_23") (pintype "bidirectional"))
    )
    (net (code "19") (name "MISO") (class "Default")
      (node (ref "D12") (pin "2") (pinfunction "2_2") (pintype "passive"))
      (node (ref "J4") (pin "P7") (pinfunction "DAT0_P7") (pintype "bidirectional"))
      (node (ref "R8") (pin "1") (pinfunction "1_1") (pintype "passive"))
      (node (ref "TP6") (pin "TP") (pinfunction "TP_TP") (pintype "input"))
      (node (ref "U1") (pin "2") (pinfunction "DO(IO1)_2") (pintype "bidirectional"))
      (node (ref "U2") (pin "27") (pinfunction "IO2_27") (pintype "bidirectional"))
    )
    (net (code "20") (name "MOSI") (class "Default")
      (node (ref "D11") (pin "2") (pinfunction "2_2") (pintype "passive"))
      (node (ref "FH34SRJ-24S-0.5SH_99_") (pin "14") (pinfunction "14_14") (pintype "bidirectional"))
      (node (ref "J4") (pin "P3") (pinfunction "CMD_P3") (pintype "bidirectional"))
      (node (ref "R7") (pin "1") (pinfunction "1_1") (pintype "passive"))
      (node (ref "TP7") (pin "TP") (pinfunction "TP_TP") (pintype "input"))
      (node (ref "U1") (pin "5") (pinfunction "DI(IO0)_5") (pintype "bidirectional"))
      (node (ref "U2") (pin "7") (pinfunction "IO7_7") (pintype "bidirectional"))
    )
    (net (code "21") (name "N$12") (class "Default")
      (node (ref "EPD_C5") (pin "2") (pinfunction "2_2") (pintype "passive"))
      (node (ref "FH34SRJ-24S-0.5SH_99_") (pin "15") (pinfunction "15_15") (pintype "bidirectional"))
      (node (ref "FH34SRJ-24S-0.5SH_99_") (pin "16") (pinfunction "16_16") (pintype "bidirectional"))
    )
    (net (code "22") (name "Net-(CHG_LED-PadC)") (class "Default")
      (node (ref "CHG_LED") (pin "C") (pinfunction "C_C") (pintype "passive"))
      (node (ref "R1_BAT") (pin "1") (pinfunction "1_1") (pintype "passive"))
    )
    (net (code "23") (name "Net-(D2-CATHODE)") (class "Default")
      (node (ref "C1_BAT1") (pin "1") (pinfunction "1_1") (pintype "passive"))
      (node (ref "D2") (pin "1") (pinfunction "CATHODE_1") (pintype "bidirectional"))
      (node (ref "IC4") (pin "1") (pinfunction "VIN_1") (pintype "bidirectional"))
      (node (ref "IC4") (pin "3") (pinfunction "CE_3") (pintype "bidirectional"))
    )
    (net (code "24") (name "Net-(D3-A)") (class "Default")
      (node (ref "C4") (pin "1") (pinfunction "1_1") (pintype "passive"))
      (node (ref "D3") (pin "2") (pinfunction "A_2") (pintype "bidirectional"))
      (node (ref "D4") (pin "1") (pinfunction "K_1") (pintype "bidirectional"))
    )
    (net (code "25") (name "Net-(D7-CATHODE)") (class "Default")
      (node (ref "D7") (pin "1") (pinfunction "CATHODE_1") (pintype "bidirectional"))
      (node (ref "R_CAPACITOR") (pin "2") (pinfunction "2_2") (pintype "passive"))
    )
    (net (code "26") (name "Net-(EPD_C1-Pad2)") (class "Default")
      (node (ref "EPD_C1") (pin "2") (pinfunction "2_2") (pintype "passive"))
      (node (ref "FH34SRJ-24S-0.5SH_99_") (pin "4") (pinfunction "4_4") (pintype "bidirectional"))
    )
    (net (code "27") (name "Net-(EPD_C2-Pad2)") (class "Default")
      (node (ref "EPD_C2") (pin "2") (pinfunction "2_2") (pintype "passive"))
      (node (ref "FH34SRJ-24S-0.5SH_99_") (pin "5") (pinfunction "5_5") (pintype "bidirectional"))
    )
    (net (code "28") (name "Net-(EPD_C6-Pad2)") (class "Default")
      (node (ref "EPD_C6") (pin "2") (pinfunction "2_2") (pintype "passive"))
      (node (ref "FH34SRJ-24S-0.5SH_99_") (pin "18") (pinfunction "18_18") (pintype "bidirectional"))
    )
    (net (code "29") (name "Net-(EPD_C7-Pad2)") (class "Default")
      (node (ref "EPD_C7") (pin "2") (pinfunction "2_2") (pintype "passive"))
      (node (ref "FH34SRJ-24S-0.5SH_99_") (pin "19") (pinfunction "19_19") (pintype "bidirectional"))
    )
    (net (code "30") (name "Net-(EPD_C8-Pad2)") (class "Default")
      (node (ref "EPD_C8") (pin "2") (pinfunction "2_2") (pintype "passive"))
      (node (ref "FH34SRJ-24S-0.5SH_99_") (pin "20") (pinfunction "20_20") (pintype "bidirectional"))
    )
    (net (code "31") (name "Net-(EPD_C10-Pad2)") (class "Default")
      (node (ref "EPD_C10") (pin "2") (pinfunction "2_2") (pintype "passive"))
      (node (ref "FH34SRJ-24S-0.5SH_99_") (pin "22") (pinfunction "22_22") (pintype "bidirectional"))
    )
    (net (code "32") (name "Net-(EPD_C12-Pad2)") (class "Default")
      (node (ref "EPD_C12") (pin "2") (pinfunction "2_2") (pintype "passive"))
      (node (ref "FH34SRJ-24S-0.5SH_99_") (pin "24") (pinfunction "24_24") (pintype "bidirectional"))
    )
    (net (code "33") (name "Net-(IC1-CT)") (class "Default")
      (node (ref "C_DELAY") (pin "2") (pinfunction "2_2") (pintype "passive"))
      (node (ref "IC1") (pin "5") (pinfunction "CT_5") (pintype "bidirectional"))
    )
    (net (code "34") (name "Net-(J2-PadA5)") (class "Default")
      (node (ref "J2") (pin "A5") (pinfunction "A5_A5") (pintype "bidirectional"))
      (node (ref "R2_USB1") (pin "2") (pinfunction "2_2") (pintype "passive"))
    )
    (net (code "35") (name "Net-(J2-PadB5)") (class "Default")
      (node (ref "J2") (pin "B5") (pinfunction "B5_B5") (pintype "bidirectional"))
      (node (ref "R2_USB") (pin "1") (pinfunction "1_1") (pintype "passive"))
    )
    (net (code "36") (name "Net-(MCP73831-PROG)") (class "Default")
      (node (ref "MCP73831") (pin "5") (pinfunction "PROG_5") (pintype "input"))
      (node (ref "R2_BAT") (pin "2") (pinfunction "2_2") (pintype "passive"))
    )
    (net (code "37") (name "Net-(MCP73831-STAT)") (class "Default")
      (node (ref "MCP73831") (pin "1") (pinfunction "STAT_1") (pintype "output"))
      (node (ref "R1_BAT") (pin "2") (pinfunction "2_2") (pintype "passive"))
    )
    (net (code "38") (name "PREVGH") (class "Default")
      (node (ref "D5") (pin "1") (pinfunction "K_1") (pintype "bidirectional"))
      (node (ref "EPD_C9") (pin "2") (pinfunction "2_2") (pintype "passive"))
      (node (ref "FH34SRJ-24S-0.5SH_99_") (pin "21") (pinfunction "21_21") (pintype "bidirectional"))
    )
    (net (code "39") (name "PREVGL") (class "Default")
      (node (ref "D4") (pin "2") (pinfunction "A_2") (pintype "bidirectional"))
      (node (ref "EPD_C11") (pin "2") (pinfunction "2_2") (pintype "passive"))
      (node (ref "FH34SRJ-24S-0.5SH_99_") (pin "23") (pinfunction "23_23") (pintype "bidirectional"))
    )
    (net (code "40") (name "RESE") (class "Default")
      (node (ref "FH34SRJ-24S-0.5SH_99_") (pin "3") (pinfunction "3_3") (pintype "bidirectional"))
      (node (ref "Q3") (pin "2") (pinfunction "S_2") (pintype "bidirectional"))
      (node (ref "R3") (pin "2") (pinfunction "2_2") (pintype "passive"))
    )
    (net (code "41") (name "RESE'") (class "Default")
      (node (ref "R2") (pin "2") (pinfunction "2_2") (pintype "passive"))
      (node (ref "R3") (pin "1") (pinfunction "1_1") (pintype "passive"))
      (node (ref "SJ1") (pin "2") (pinfunction "2_2") (pintype "passive"))
    )
    (net (code "42") (name "RESET") (class "Default")
      (node (ref "C5") (pin "1") (pinfunction "1_1") (pintype "passive"))
      (node (ref "IC1") (pin "1") (pinfunction "VOUT_1") (pintype "bidirectional"))
      (node (ref "RESET_BUTTON") (pin "4") (pinfunction "4_4") (pintype "passive"))
      (node (ref "R_RESET") (pin "1") (pinfunction "1_1") (pintype "passive"))
      (node (ref "U2") (pin "3") (pinfunction "EN_3") (pintype "input"))
    )
    (net (code "43") (name "RTC_RST") (class "Default")
      (node (ref "U2") (pin "16") (pinfunction "IO18_16") (pintype "bidirectional"))
      (node (ref "U3") (pin "4") (pinfunction "~{RST}_4") (pintype "input"))
    )
    (net (code "44") (name "RX") (class "Default")
      (node (ref "TP2") (pin "TP") (pinfunction "TP_TP") (pintype "input"))
      (node (ref "U2") (pin "24") (pinfunction "RXD0/GPIO17_24") (pintype "bidirectional"))
    )
    (net (code "45") (name "SCK") (class "Default")
      (node (ref "D10") (pin "2") (pinfunction "2_2") (pintype "passive"))
      (node (ref "FH34SRJ-24S-0.5SH_99_") (pin "13") (pinfunction "13_13") (pintype "bidirectional"))
      (node (ref "J4") (pin "P5") (pinfunction "CLK_P5") (pintype "bidirectional"))
      (node (ref "R6") (pin "1") (pinfunction "1_1") (pintype "passive"))
      (node (ref "TP8") (pin "TP") (pinfunction "TP_TP") (pintype "input"))
      (node (ref "U1") (pin "6") (pinfunction "CLK_6") (pintype "input"))
      (node (ref "U2") (pin "6") (pinfunction "IO6_6") (pintype "bidirectional"))
    )
    (net (code "46") (name "SCL") (class "Default")
      (node (ref "J3") (pin "4") (pinfunction "4_4") (pintype "passive"))
      (node (ref "R2_PINH") (pin "1") (pinfunction "1_1") (pintype "passive"))
      (node (ref "SENSOR2") (pin "4") (pinfunction "SCK_4") (pintype "input"))
      (node (ref "U2") (pin "20") (pinfunction "IO22_20") (pintype "bidirectional"))
      (node (ref "U3") (pin "16") (pinfunction "SCL_16") (pintype "input"))
      (node (ref "U4") (pin "7") (pinfunction "SCL_7") (pintype "input"))
    )
    (net (code "47") (name "SDA") (class "Default")
      (node (ref "J3") (pin "3") (pinfunction "3_3") (pintype "passive"))
      (node (ref "R1_PINH") (pin "1") (pinfunction "1_1") (pintype "passive"))
      (node (ref "SENSOR2") (pin "3") (pinfunction "SDI_3") (pintype "bidirectional"))
      (node (ref "U2") (pin "19") (pinfunction "IO21_19") (pintype "bidirectional"))
      (node (ref "U3") (pin "15") (pinfunction "SDA_15") (pintype "bidirectional"))
      (node (ref "U4") (pin "8") (pinfunction "SDA_8") (pintype "bidirectional"))
    )
    (net (code "48") (name "SRC") (class "Default")
      (node (ref "C4") (pin "2") (pinfunction "2_2") (pintype "passive"))
      (node (ref "D5") (pin "2") (pinfunction "A_2") (pintype "bidirectional"))
      (node (ref "L1") (pin "1") (pinfunction "1_1") (pintype "passive"))
      (node (ref "Q3") (pin "3") (pinfunction "D_3") (pintype "bidirectional"))
    )
    (net (code "49") (name "SS_SD") (class "Default")
      (node (ref "D8") (pin "2") (pinfunction "2_2") (pintype "passive"))
      (node (ref "J4") (pin "P2") (pinfunction "CD/DAT3_P2") (pintype "bidirectional"))
      (node (ref "R10") (pin "1") (pinfunction "1_1") (pintype "passive"))
      (node (ref "U2") (pin "4") (pinfunction "IO4_4") (pintype "bidirectional"))
    )
    (net (code "50") (name "TX") (class "Default")
      (node (ref "TP1") (pin "TP") (pinfunction "TP_TP") (pintype "input"))
      (node (ref "U2") (pin "25") (pinfunction "TXD0/GPIO16_25") (pintype "bidirectional"))
    )
    (net (code "51") (name "USB_D+") (class "Default")
      (node (ref "D1") (pin "3") (pinfunction "I/O2_1_3") (pintype "bidirectional"))
      (node (ref "U2") (pin "14") (pinfunction "IO13_14") (pintype "bidirectional"))
    )
    (net (code "52") (name "USB_D-") (class "Default")
      (node (ref "D1") (pin "1") (pinfunction "I/O1_1_1") (pintype "bidirectional"))
      (node (ref "U2") (pin "13") (pinfunction "IO12_13") (pintype "bidirectional"))
    )
    (net (code "53") (name "VBAT") (class "Default")
      (node (ref "C2_BAT") (pin "1") (pinfunction "1_1") (pintype "passive"))
      (node (ref "MCP73831") (pin "3") (pinfunction "VBAT_3") (pintype "power_in"))
      (node (ref "TP3") (pin "TP") (pinfunction "TP_TP") (pintype "input"))
      (node (ref "U4") (pin "2") (pinfunction "CELL_2") (pintype "power_in"))
      (node (ref "U4") (pin "3") (pinfunction "VDD_3") (pintype "power_in"))
    )
    (net (code "54") (name "VBUS") (class "Default")
      (node (ref "C1_BAT") (pin "1") (pinfunction "1_1") (pintype "passive"))
      (node (ref "C4_USB") (pin "1") (pinfunction "1_1") (pintype "passive"))
      (node (ref "C5_USB") (pin "1") (pinfunction "1_1") (pintype "passive"))
      (node (ref "CHG_LED") (pin "A") (pinfunction "A_A") (pintype "passive"))
      (node (ref "D1") (pin "5") (pinfunction "VBUS_5") (pintype "bidirectional"))
      (node (ref "D2") (pin "2") (pinfunction "ANODE_2") (pintype "bidirectional"))
      (node (ref "MCP73831") (pin "4") (pinfunction "VIN_4") (pintype "power_in"))
      (node (ref "PFMF.050.1") (pin "2") (pinfunction "2_2") (pintype "passive"))
      (node (ref "Q1") (pin "1") (pinfunction "G_1") (pintype "bidirectional"))
      (node (ref "Q1") (pin "3") (pinfunction "D_3") (pintype "bidirectional"))
      (node (ref "R1_PWRUSB") (pin "2") (pinfunction "2_2") (pintype "passive"))
      (node (ref "TP14") (pin "TP") (pinfunction "TP_TP") (pintype "input"))
    )
    (net (code "55") (name "VRTC") (class "Default")
      (node (ref "C10_SUPERCAP") (pin "1") (pinfunction "1_1") (pintype "passive"))
      (node (ref "C8") (pin "1") (pinfunction "1_1") (pintype "passive"))
      (node (ref "R_CAPACITOR") (pin "1") (pinfunction "1_1") (pintype "passive"))
      (node (ref "U3") (pin "14") (pinfunction "VBAT_14") (pintype "power_in"))
    )
    (net (code "56") (name "VUSB") (class "Default")
      (node (ref "J2") (pin "A4") (pinfunction "A4_A4") (pintype "bidirectional"))
      (node (ref "J2") (pin "A9") (pinfunction "A9_A9") (pintype "bidirectional"))
      (node (ref "J2") (pin "B4") (pinfunction "B4_B4") (pintype "bidirectional"))
      (node (ref "J2") (pin "B9") (pinfunction "B9_B9") (pintype "bidirectional"))
      (node (ref "PFMF.050.1") (pin "1") (pinfunction "1_1") (pintype "passive"))
    )
    (net (code "57") (name "unconnected-(BOOT_BUTTON1-Pad1)") (class "Default")
      (node (ref "BOOT_BUTTON1") (pin "1") (pinfunction "1_1") (pintype "passive"))
    )
    (net (code "58") (name "unconnected-(BOOT_BUTTON1-Pad3)") (class "Default")
      (node (ref "BOOT_BUTTON1") (pin "3") (pinfunction "3_3") (pintype "passive"))
    )
    (net (code "59") (name "unconnected-(CHANGE_BUTTON2-Pad1)") (class "Default")
      (node (ref "CHANGE_BUTTON2") (pin "1") (pinfunction "1_1") (pintype "passive"))
    )
    (net (code "60") (name "unconnected-(CHANGE_BUTTON2-Pad3)") (class "Default")
      (node (ref "CHANGE_BUTTON2") (pin "3") (pinfunction "3_3") (pintype "passive"))
    )
    (net (code "61") (name "unconnected-(FH34SRJ-24S-0.5SH_99_-Pad1)") (class "Default")
      (node (ref "FH34SRJ-24S-0.5SH_99_") (pin "1") (pinfunction "1_1") (pintype "bidirectional"))
    )
    (net (code "62") (name "unconnected-(FH34SRJ-24S-0.5SH_99_-Pad6)") (class "Default")
      (node (ref "FH34SRJ-24S-0.5SH_99_") (pin "6") (pinfunction "6_6") (pintype "bidirectional"))
    )
    (net (code "63") (name "unconnected-(FH34SRJ-24S-0.5SH_99_-Pad7)") (class "Default")
      (node (ref "FH34SRJ-24S-0.5SH_99_") (pin "7") (pinfunction "7_7") (pintype "bidirectional"))
    )
    (net (code "64") (name "unconnected-(IC1-NC-Pad4)") (class "Default")
      (node (ref "IC1") (pin "4") (pinfunction "NC_4") (pintype "no_connect"))
    )
    (net (code "65") (name "unconnected-(IC4-NC-Pad4)") (class "Default")
      (node (ref "IC4") (pin "4") (pinfunction "NC_4") (pintype "no_connect"))
    )
    (net (code "66") (name "unconnected-(J2-PadA6)") (class "Default")
      (node (ref "J2") (pin "A6") (pinfunction "A6_A6") (pintype "bidirectional"))
    )
    (net (code "67") (name "unconnected-(J2-PadB8)") (class "Default")
      (node (ref "J2") (pin "B8") (pinfunction "B8_B8") (pintype "bidirectional"))
    )
    (net (code "68") (name "unconnected-(J4-DAT1-PadP8)") (class "Default")
      (node (ref "J4") (pin "P8") (pinfunction "DAT1_P8") (pintype "bidirectional"))
    )
    (net (code "69") (name "unconnected-(J4-DAT2-PadP1)") (class "Default")
      (node (ref "J4") (pin "P1") (pinfunction "DAT2_P1") (pintype "bidirectional"))
    )
    (net (code "70") (name "unconnected-(J4-DETECTION_1-PadS1)") (class "Default")
      (node (ref "J4") (pin "S1") (pinfunction "DETECTION_1_S1") (pintype "bidirectional"))
    )
    (net (code "71") (name "unconnected-(J4-DETECTION_2-PadS2)") (class "Default")
      (node (ref "J4") (pin "S2") (pinfunction "DETECTION_2_S2") (pintype "bidirectional"))
    )
    (net (code "72") (name "unconnected-(Q1-S-Pad2)") (class "Default")
      (node (ref "Q1") (pin "2") (pinfunction "S_2") (pintype "bidirectional"))
    )
    (net (code "73") (name "unconnected-(RESET_BUTTON-Pad1)") (class "Default")
      (node (ref "RESET_BUTTON") (pin "1") (pinfunction "1_1") (pintype "passive"))
    )
    (net (code "74") (name "unconnected-(RESET_BUTTON-Pad3)") (class "Default")
      (node (ref "RESET_BUTTON") (pin "3") (pinfunction "3_3") (pintype "passive"))
    )
    (net (code "75") (name "unconnected-(U2-NC-Pad22)") (class "Default")
      (node (ref "U2") (pin "22") (pinfunction "NC_22") (pintype "no_connect"))
    )
    (net (code "76") (name "unconnected-(U4-~{ALERT}-Pad5)") (class "Default")
      (node (ref "U4") (pin "5") (pinfunction "~{ALERT}_5") (pintype "output"))
    )
  )
)
